# MP4462_MP4560_AllCanUse.net
KiCad netlist of a schematic drawn in Altium Designer
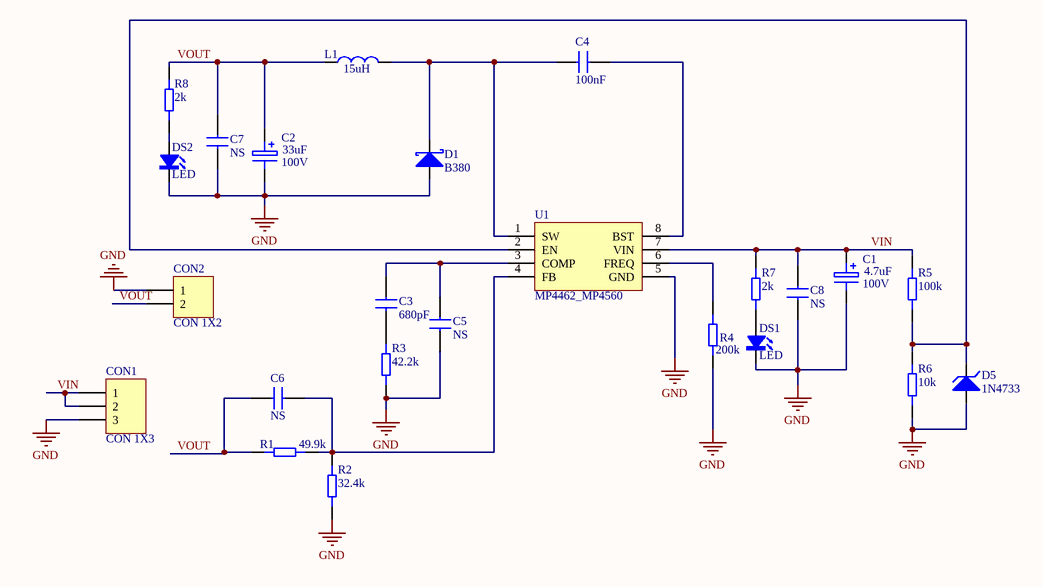
[diagram p0: MP4462_MP4560_AllCanUse.SchDoc]

(export (version "E")
  (design (tool "Eeschema 10.0.6"))
  (components
    (comp (ref "C1")
      (value "4.7uF")
      (footprint "C-E-5X10X12mm")
      (description "电解电容")
      (fields
        (field (name "RATED VOLTAGE") "100V")
        (field (name "TOLERANCE") "20%")
        (field (name "MANUFACTURER") "Rubycon红宝石")
      )
      (libsource (lib "DEVICE") (part "CAP-E"))
    )
    (comp (ref "C2")
      (value "33uF")
      (footprint "C-E-5X10X12mm")
      (description "电解电容")
      (fields
        (field (name "RATED VOLTAGE") "100V")
        (field (name "TOLERANCE") "20%")
        (field (name "MANUFACTURER") "Rubycon红宝石")
      )
      (libsource (lib "DEVICE") (part "CAP-E"))
    )
    (comp (ref "C3")
      (value "680pF")
      (footprint "C0805")
      (description "SMD-CAP（陶瓷电容）")
      (fields (field (name "TOLERANCE") "20%") (field (name "MANUFACTURER") "muRata村田"))
      (libsource (lib "5D_DEVICE") (part "CAP-SMD"))
    )
    (comp (ref "C4")
      (value "100nF")
      (footprint "C0805")
      (description "SMD-CAP（陶瓷电容）")
      (fields (field (name "TOLERANCE") "20%") (field (name "MANUFACTURER") "muRata村田"))
      (libsource (lib "5D_DEVICE") (part "CAP-SMD"))
    )
    (comp (ref "C5")
      (value "NS")
      (footprint "C0805")
      (description "SMD-CAP（陶瓷电容）")
      (fields (field (name "TOLERANCE") "20%") (field (name "MANUFACTURER") "muRata村田"))
      (libsource (lib "5D_DEVICE") (part "CAP-SMD"))
    )
    (comp (ref "C6")
      (value "NS")
      (footprint "C0805")
      (description "SMD-CAP（陶瓷电容）")
      (fields (field (name "TOLERANCE") "20%") (field (name "MANUFACTURER") "muRata村田"))
      (libsource (lib "5D_DEVICE") (part "CAP-SMD"))
    )
    (comp (ref "C7")
      (value "NS")
      (footprint "C0805")
      (description "SMD-CAP（陶瓷电容）")
      (fields (field (name "TOLERANCE") "20%") (field (name "MANUFACTURER") "muRata村田"))
      (libsource (lib "5D_DEVICE") (part "CAP-SMD"))
    )
    (comp (ref "C8")
      (value "NS")
      (footprint "C0805")
      (description "SMD-CAP（陶瓷电容）")
      (fields (field (name "TOLERANCE") "20%") (field (name "MANUFACTURER") "muRata村田"))
      (libsource (lib "5D_DEVICE") (part "CAP-SMD"))
    )
    (comp (ref "CON1")
      (value "CON 1X3")
      (footprint "KF128-5.08mm-3P")
      (libsource (lib "CONNECTOR") (part "CON 1X3"))
    )
    (comp (ref "CON2")
      (value "CON 1X2")
      (footprint "KF128-5.08mm-2P")
      (libsource (lib "CONNECTOR") (part "CON 1X2"))
    )
    (comp (ref "D1")
      (value "B380")
      (footprint "LC-SMB(DO-214AA)_S1")
      (description "Diode Schottky")
      (libsource (lib "DEVICE") (part "D-Schottky"))
    )
    (comp (ref "D5")
      (value "1N4733")
      (footprint "SOD-123")
      (description "Diode Manostat")
      (libsource (lib "DEVICE") (part "D-Manostat"))
    )
    (comp (ref "DS1") (value "LED") (footprint "LED-0805") (libsource (lib "DEVICE") (part "LED")))
    (comp (ref "DS2") (value "LED") (footprint "LED-0805") (libsource (lib "DEVICE") (part "LED")))
    (comp (ref "L1")
      (value "L-SMD")
      (footprint "SLF12575T")
      (description "Inductor")
      (fields (field (name "ALTIUM_UNNAMED_1") "15uH"))
      (libsource (lib "DEVICE") (part "L-SMD"))
    )
    (comp (ref "R1")
      (value "49.9k")
      (footprint "R0805")
      (description "Resistor")
      (fields (field (name "TOLERANCE") "5%") (field (name "MANUFACTURER") "SAMSUNG三星"))
      (libsource (lib "DEVICE") (part "RES"))
    )
    (comp (ref "R2")
      (value "32.4k")
      (footprint "R0805")
      (description "Resistor")
      (fields (field (name "TOLERANCE") "5%") (field (name "MANUFACTURER") "SAMSUNG三星"))
      (libsource (lib "DEVICE") (part "RES"))
    )
    (comp (ref "R3")
      (value "42.2k")
      (footprint "R0805")
      (description "Resistor")
      (fields (field (name "TOLERANCE") "5%") (field (name "MANUFACTURER") "SAMSUNG三星"))
      (libsource (lib "DEVICE") (part "RES"))
    )
    (comp (ref "R4")
      (value "200k")
      (footprint "R0805")
      (description "Resistor")
      (fields (field (name "TOLERANCE") "5%") (field (name "MANUFACTURER") "SAMSUNG三星"))
      (libsource (lib "DEVICE") (part "RES"))
    )
    (comp (ref "R5")
      (value "100k")
      (footprint "R0805")
      (description "Resistor")
      (fields (field (name "TOLERANCE") "5%") (field (name "MANUFACTURER") "SAMSUNG三星"))
      (libsource (lib "DEVICE") (part "RES"))
    )
    (comp (ref "R6")
      (value "10k")
      (footprint "R0805")
      (description "Resistor")
      (fields (field (name "TOLERANCE") "5%") (field (name "MANUFACTURER") "SAMSUNG三星"))
      (libsource (lib "DEVICE") (part "RES"))
    )
    (comp (ref "R7")
      (value "2k")
      (footprint "R0805")
      (description "Resistor")
      (fields (field (name "TOLERANCE") "5%") (field (name "MANUFACTURER") "SAMSUNG三星"))
      (libsource (lib "DEVICE") (part "RES"))
    )
    (comp (ref "R8")
      (value "2k")
      (footprint "R0805")
      (description "Resistor")
      (fields (field (name "TOLERANCE") "5%") (field (name "MANUFACTURER") "SAMSUNG三星"))
      (libsource (lib "DEVICE") (part "RES"))
    )
    (comp (ref "U1")
      (value "MP4462_MP4560")
      (footprint "LC-SOIC-8_EP_150mil")
      (libsource (lib "MP4462_MP4560_AllCanUse_SOIC8") (part "MP4462_MP4560"))
    )
  )
  (nets
    (net (code "1") (name "/VIN") (class "Default")
      (node (ref "C1") (pin "1") (pinfunction "1_1") (pintype "passive"))
      (node (ref "C8") (pin "1") (pinfunction "1_1") (pintype "passive"))
      (node (ref "CON1") (pin "1") (pinfunction "1_1") (pintype "passive"))
      (node (ref "CON1") (pin "2") (pinfunction "2_2") (pintype "passive"))
      (node (ref "R5") (pin "2") (pinfunction "2_2") (pintype "passive"))
      (node (ref "R7") (pin "2") (pinfunction "2_2") (pintype "passive"))
      (node (ref "U1") (pin "7") (pinfunction "VIN_7") (pintype "passive"))
    )
    (net (code "2") (name "/VOUT") (class "Default")
      (node (ref "C2") (pin "1") (pinfunction "1_1") (pintype "passive"))
      (node (ref "C6") (pin "1") (pinfunction "1_1") (pintype "passive"))
      (node (ref "C7") (pin "1") (pinfunction "1_1") (pintype "passive"))
      (node (ref "CON2") (pin "2") (pinfunction "2_2") (pintype "passive"))
      (node (ref "L1") (pin "1") (pinfunction "1_1") (pintype "passive"))
      (node (ref "R1") (pin "2") (pinfunction "2_2") (pintype "passive"))
      (node (ref "R8") (pin "2") (pinfunction "2_2") (pintype "passive"))
    )
    (net (code "3") (name "GND") (class "Default")
      (node (ref "C1") (pin "2") (pinfunction "2_2") (pintype "passive"))
      (node (ref "C2") (pin "2") (pinfunction "2_2") (pintype "passive"))
      (node (ref "C5") (pin "2") (pinfunction "2_2") (pintype "passive"))
      (node (ref "C7") (pin "2") (pinfunction "2_2") (pintype "passive"))
      (node (ref "C8") (pin "2") (pinfunction "2_2") (pintype "passive"))
      (node (ref "CON1") (pin "3") (pinfunction "3_3") (pintype "passive"))
      (node (ref "CON2") (pin "1") (pinfunction "1_1") (pintype "passive"))
      (node (ref "D1") (pin "1") (pinfunction "1_1") (pintype "passive"))
      (node (ref "D5") (pin "1") (pinfunction "1_1") (pintype "passive"))
      (node (ref "DS1") (pin "K") (pinfunction "K_K") (pintype "passive"))
      (node (ref "DS2") (pin "K") (pinfunction "K_K") (pintype "passive"))
      (node (ref "R2") (pin "1") (pinfunction "1_1") (pintype "passive"))
      (node (ref "R3") (pin "1") (pinfunction "1_1") (pintype "passive"))
      (node (ref "R4") (pin "1") (pinfunction "1_1") (pintype "passive"))
      (node (ref "R6") (pin "1") (pinfunction "1_1") (pintype "passive"))
      (node (ref "U1") (pin "5") (pinfunction "GND_5") (pintype "passive"))
    )
    (net (code "4") (name "Net-(C3-Pad2)") (class "Default")
      (node (ref "C3") (pin "2") (pinfunction "2_2") (pintype "passive"))
      (node (ref "R3") (pin "2") (pinfunction "2_2") (pintype "passive"))
    )
    (net (code "5") (name "Net-(DS1-PadA)") (class "Default")
      (node (ref "DS1") (pin "A") (pinfunction "A_A") (pintype "passive"))
      (node (ref "R7") (pin "1") (pinfunction "1_1") (pintype "passive"))
    )
    (net (code "6") (name "Net-(DS2-PadA)") (class "Default")
      (node (ref "DS2") (pin "A") (pinfunction "A_A") (pintype "passive"))
      (node (ref "R8") (pin "1") (pinfunction "1_1") (pintype "passive"))
    )
    (net (code "7") (name "Net-(U1-BST)") (class "Default")
      (node (ref "C4") (pin "2") (pinfunction "2_2") (pintype "passive"))
      (node (ref "U1") (pin "8") (pinfunction "BST_8") (pintype "passive"))
    )
    (net (code "8") (name "Net-(U1-COMP)") (class "Default")
      (node (ref "C3") (pin "1") (pinfunction "1_1") (pintype "passive"))
      (node (ref "C5") (pin "1") (pinfunction "1_1") (pintype "passive"))
      (node (ref "U1") (pin "3") (pinfunction "COMP_3") (pintype "passive"))
    )
    (net (code "9") (name "Net-(U1-EN)") (class "Default")
      (node (ref "D5") (pin "2") (pinfunction "2_2") (pintype "passive"))
      (node (ref "R5") (pin "1") (pinfunction "1_1") (pintype "passive"))
      (node (ref "R6") (pin "2") (pinfunction "2_2") (pintype "passive"))
      (node (ref "U1") (pin "2") (pinfunction "EN_2") (pintype "passive"))
    )
    (net (code "10") (name "Net-(U1-FB)") (class "Default")
      (node (ref "C6") (pin "2") (pinfunction "2_2") (pintype "passive"))
      (node (ref "R1") (pin "1") (pinfunction "1_1") (pintype "passive"))
      (node (ref "R2") (pin "2") (pinfunction "2_2") (pintype "passive"))
      (node (ref "U1") (pin "4") (pinfunction "FB_4") (pintype "passive"))
    )
    (net (code "11") (name "Net-(U1-FREQ)") (class "Default")
      (node (ref "R4") (pin "2") (pinfunction "2_2") (pintype "passive"))
      (node (ref "U1") (pin "6") (pinfunction "FREQ_6") (pintype "passive"))
    )
    (net (code "12") (name "Net-(U1-SW)") (class "Default")
      (node (ref "C4") (pin "1") (pinfunction "1_1") (pintype "passive"))
      (node (ref "D1") (pin "2") (pinfunction "2_2") (pintype "passive"))
      (node (ref "L1") (pin "2") (pinfunction "2_2") (pintype "passive"))
      (node (ref "U1") (pin "1") (pinfunction "SW_1") (pintype "passive"))
    )
  )
)
